# uMultimeter_LED_Sch.net
KiCad netlist of a schematic drawn in Altium Designer
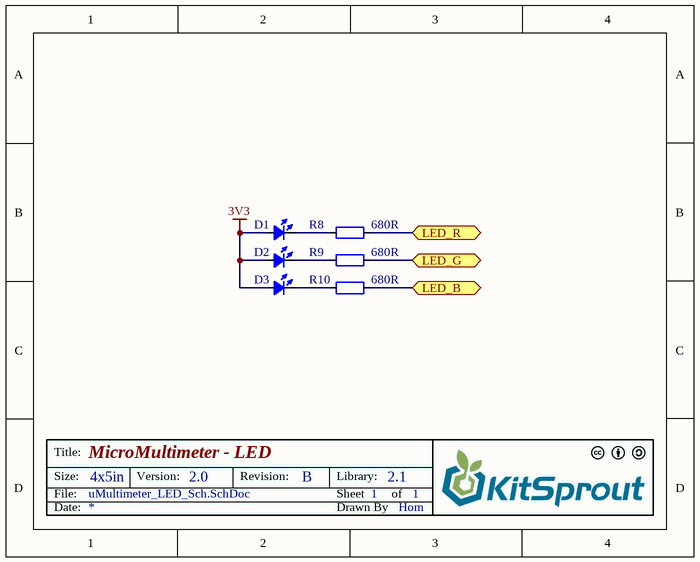
[diagram p0: uMultimeter_LED_Sch.SchDoc]

(export (version "E")
  (design (tool "Eeschema 10.0.6"))
  (components
    (comp (ref "D1")
      (value "LED_0805")
      (footprint "PCB_ActiveLED:LED_0805_RED")
      (description "LED")
      (libsource (lib "SCH_Active") (part "LED_0805"))
    )
    (comp (ref "D2")
      (value "LED_0805")
      (footprint "PCB_ActiveLED:LED_0805_GREEN")
      (description "LED")
      (libsource (lib "SCH_Active") (part "LED_0805"))
    )
    (comp (ref "D3")
      (value "LED_0805")
      (footprint "PCB_ActiveLED:LED_0805_BLUE")
      (description "LED")
      (libsource (lib "SCH_Active") (part "LED_0805"))
    )
    (comp (ref "R8")
      (value "680R")
      (footprint "PCB_PassiveRes:RES_0603")
      (description "Resistor")
      (fields (field (name "Comment") "Res_0603"))
      (libsource (lib "") (part "Res_0603_1"))
    )
    (comp (ref "R9")
      (value "680R")
      (footprint "PCB_PassiveRes:RES_0603")
      (description "Resistor")
      (fields (field (name "Comment") "Res_0603"))
      (libsource (lib "") (part "Res_0603_1"))
    )
    (comp (ref "R10")
      (value "680R")
      (footprint "PCB_PassiveRes:RES_0603")
      (description "Resistor")
      (fields (field (name "Comment") "Res_0603"))
      (libsource (lib "SCH_Passive") (part "Res_0603"))
    )
  )
  (nets
    (net (code "1") (name "/LED_B") (class "Default")
      (node (ref "R10") (pin "2") (pinfunction "2_2") (pintype "passive"))
    )
    (net (code "2") (name "/LED_G") (class "Default")
      (node (ref "R9") (pin "1") (pinfunction "1_1") (pintype "passive"))
    )
    (net (code "3") (name "/LED_R") (class "Default")
      (node (ref "R8") (pin "1") (pinfunction "1_1") (pintype "passive"))
    )
    (net (code "4") (name "3V3") (class "Default")
      (node (ref "D1") (pin "1") (pinfunction "A_1") (pintype "passive"))
      (node (ref "D2") (pin "1") (pinfunction "A_1") (pintype "passive"))
      (node (ref "D3") (pin "1") (pinfunction "A_1") (pintype "passive"))
    )
    (net (code "5") (name "Net-(D1-K)") (class "Default")
      (node (ref "D1") (pin "2") (pinfunction "K_2") (pintype "passive"))
      (node (ref "R8") (pin "2") (pinfunction "2_2") (pintype "passive"))
    )
    (net (code "6") (name "Net-(D2-K)") (class "Default")
      (node (ref "D2") (pin "2") (pinfunction "K_2") (pintype "passive"))
      (node (ref "R9") (pin "2") (pinfunction "2_2") (pintype "passive"))
    )
    (net (code "7") (name "Net-(D3-K)") (class "Default")
      (node (ref "D3") (pin "2") (pinfunction "K_2") (pintype "passive"))
      (node (ref "R10") (pin "1") (pinfunction "1_1") (pintype "passive"))
    )
  )
)
